# 4_mcu_radio_1.net
KiCad netlist of a schematic drawn in Altium Designer
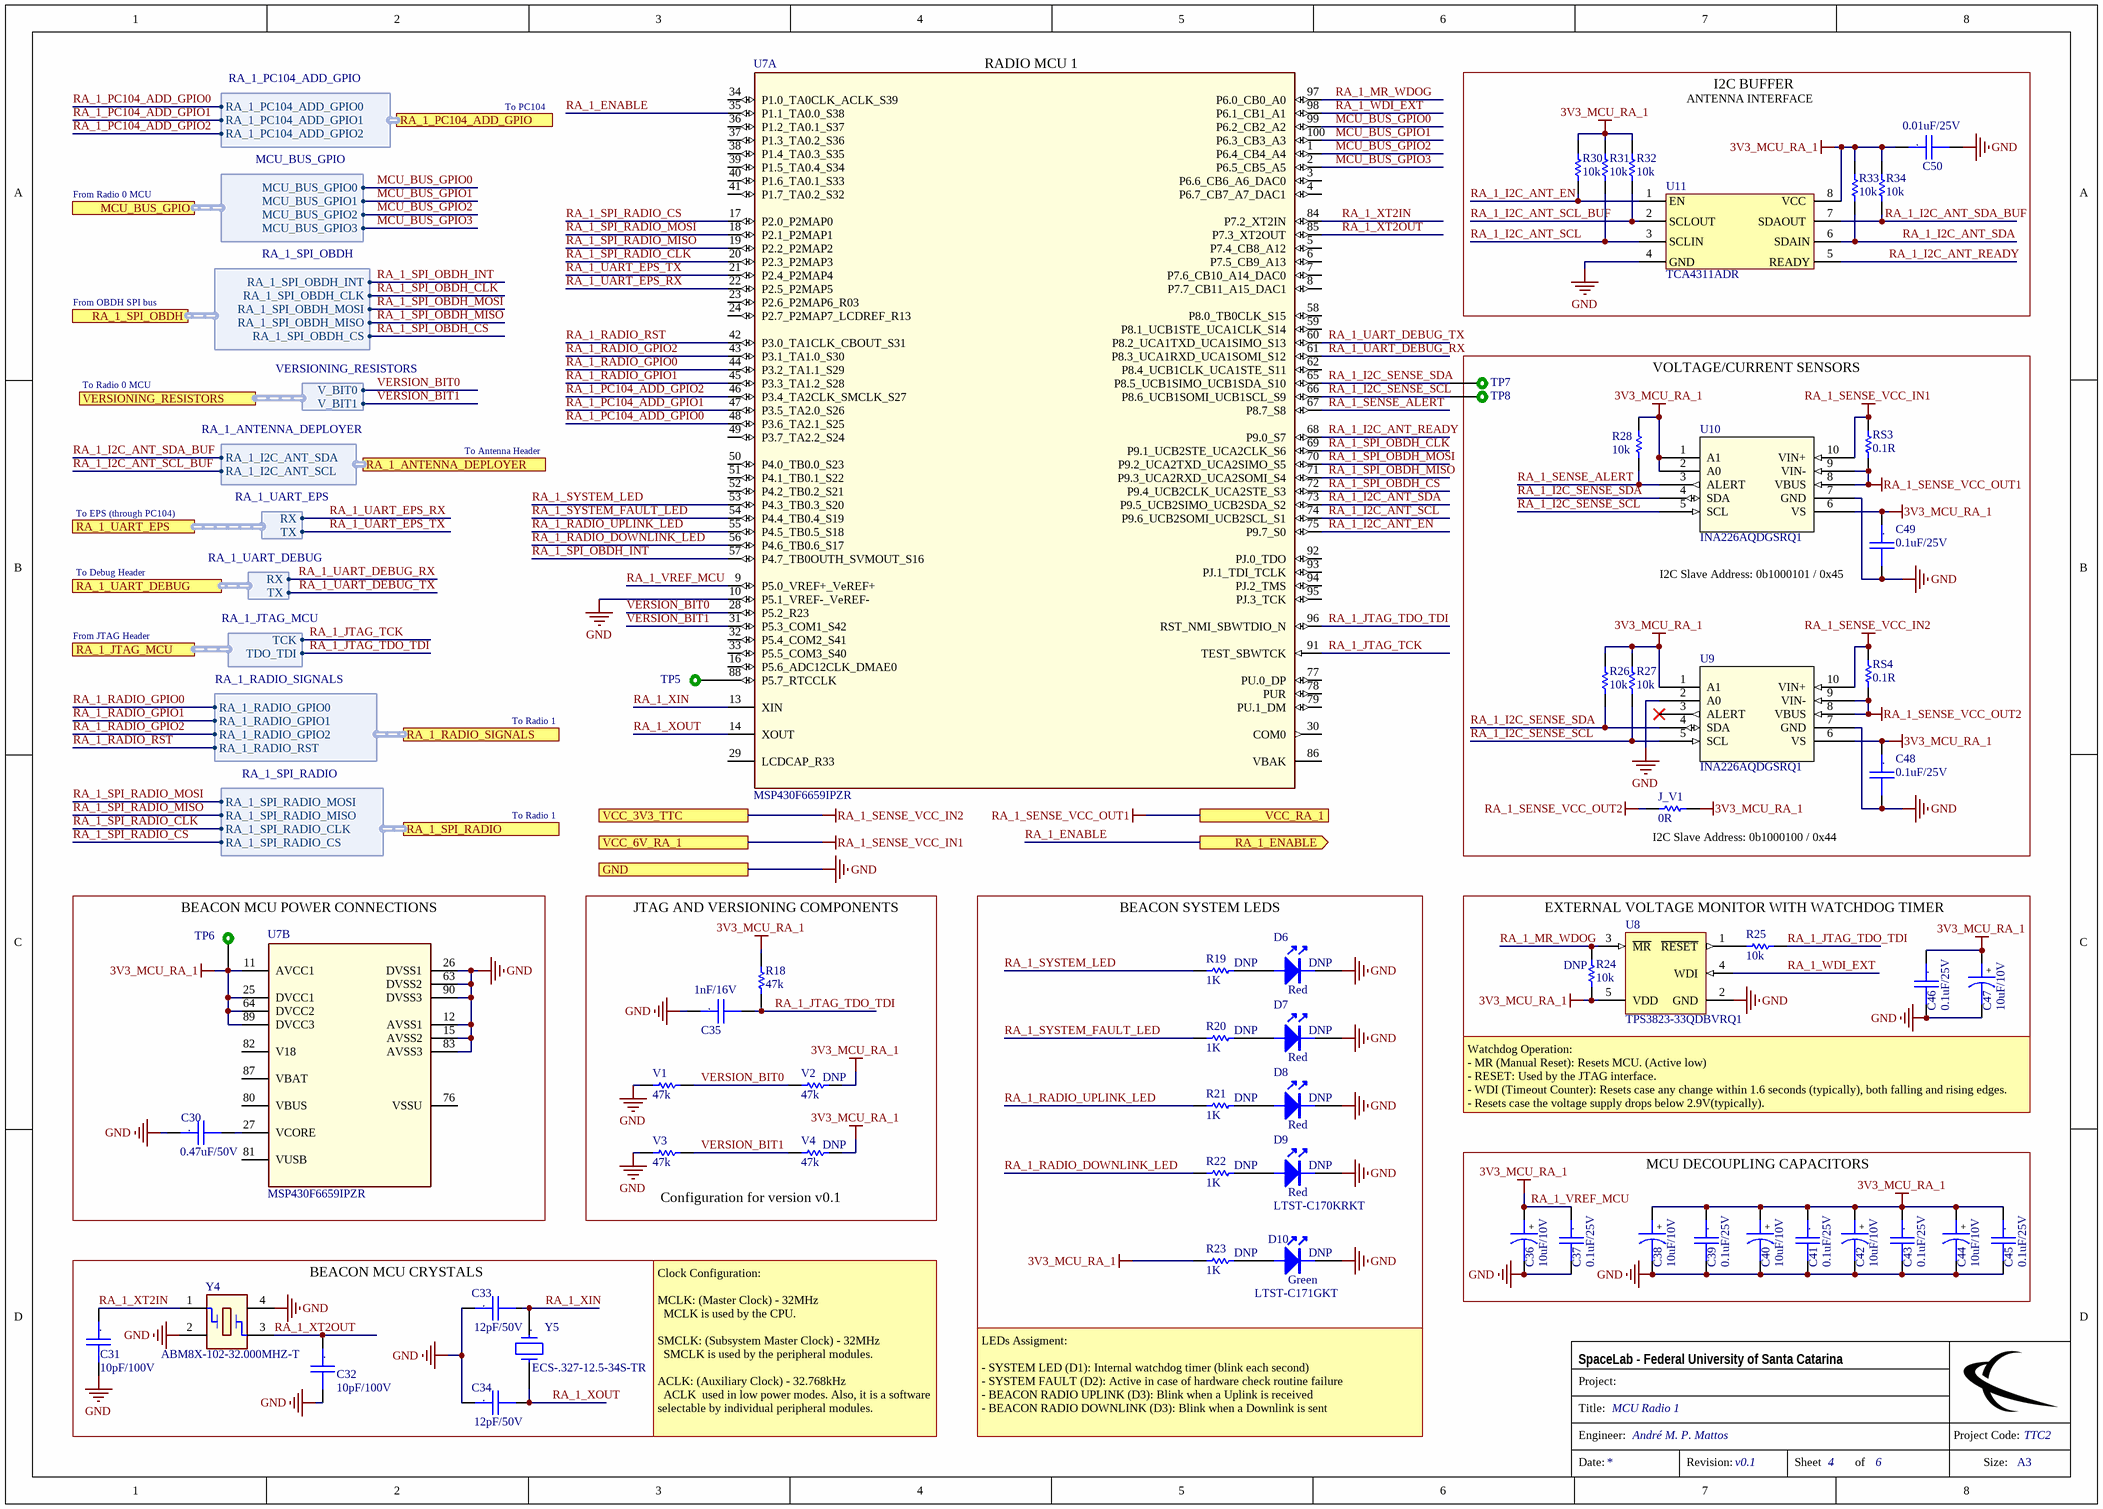
[diagram p0: 4_mcu_radio_1.schdoc]

(export (version "E")
  (design (tool "Eeschema 10.0.6"))
  (components
    (comp (ref "C30")
      (value "0.47uF/50V")
      (footprint "CC0805")
      (description "CAP CER 0.47UF 50V 10% X7R 0805")
      (fields (field (name "PARTNUMBER") "C0805C474K5RACTU"))
      (libsource (lib "schematics_library_legacy") (part "Cap_Cer_X7R_0.47uF_50V_0805"))
    )
    (comp (ref "C31")
      (value "10pF/100V")
      (footprint "CC0805")
      (description "CAP CER 10pF 100V 0805")
      (fields (field (name "PARTNUMBER") "08051A100FAT2A"))
      (libsource (lib "schematics_library_legacy") (part "Cap_Cer_X7R_10pF_100V_0805"))
    )
    (comp (ref "C32")
      (value "10pF/100V")
      (footprint "CC0805")
      (description "CAP CER 10pF 100V 0805")
      (fields (field (name "PARTNUMBER") "08051A100FAT2A"))
      (libsource (lib "schematics_library_legacy") (part "Cap_Cer_X7R_10pF_100V_0805"))
    )
    (comp (ref "C33")
      (value "12pF/50V")
      (footprint "CC0805")
      (description "CAP CER 12pF 50V 0805")
      (fields (field (name "PARTNUMBER") "CL21C120FBANNNC"))
      (libsource (lib "schematics_library_legacy") (part "Cap_Cer_X7R_12pF_50V_0805"))
    )
    (comp (ref "C34")
      (value "12pF/50V")
      (footprint "CC0805")
      (description "CAP CER 12pF 50V 0805")
      (fields (field (name "PARTNUMBER") "CL21C120FBANNNC"))
      (libsource (lib "schematics_library_legacy") (part "Cap_Cer_X7R_12pF_50V_0805"))
    )
    (comp (ref "C35")
      (value "1nF/16V")
      (footprint "CC0603")
      (description "CAP CER 1nF 16V 0603 5%")
      (fields (field (name "PARTNUMBER") "C0603X102J4RECAUTO"))
      (libsource (lib "schematics_library_legacy") (part "Cap_Cer_X7R_1nF_16V_0603"))
    )
    (comp (ref "C36")
      (value "10uF/10V")
      (footprint "CC0805_Tantalum")
      (description "CAP Tantalum 10uF 10V 20% 0805")
      (fields (field (name "PARTNUMBER") "TPSP106M010R2000"))
      (libsource (lib "schematics_library_legacy") (part "Cap_Tant_SMD_10uF_10V_0805"))
    )
    (comp (ref "C37")
      (value "0.1uF/25V")
      (footprint "CC0805")
      (description "CAP CER 0.1UF 25V 10% X7R 0805")
      (fields (field (name "PARTNUMBER") "CC0805KRX7R8BB104"))
      (libsource (lib "schematics_library_legacy") (part "Cap_Cer_X7R_0.1uF_25V_0805"))
    )
    (comp (ref "C38")
      (value "10uF/10V")
      (footprint "CC0805_Tantalum")
      (description "CAP Tantalum 10uF 10V 20% 0805")
      (fields (field (name "PARTNUMBER") "TPSP106M010R2000"))
      (libsource (lib "schematics_library_legacy") (part "Cap_Tant_SMD_10uF_10V_0805"))
    )
    (comp (ref "C39")
      (value "0.1uF/25V")
      (footprint "CC0805")
      (description "CAP CER 0.1UF 25V 10% X7R 0805")
      (fields (field (name "PARTNUMBER") "CC0805KRX7R8BB104"))
      (libsource (lib "schematics_library_legacy") (part "Cap_Cer_X7R_0.1uF_25V_0805"))
    )
    (comp (ref "C40")
      (value "10uF/10V")
      (footprint "CC0805_Tantalum")
      (description "CAP Tantalum 10uF 10V 20% 0805")
      (fields (field (name "PARTNUMBER") "TPSP106M010R2000"))
      (libsource (lib "schematics_library_legacy") (part "Cap_Tant_SMD_10uF_10V_0805"))
    )
    (comp (ref "C41")
      (value "0.1uF/25V")
      (footprint "CC0805")
      (description "CAP CER 0.1UF 25V 10% X7R 0805")
      (fields (field (name "PARTNUMBER") "CC0805KRX7R8BB104"))
      (libsource (lib "schematics_library_legacy") (part "Cap_Cer_X7R_0.1uF_25V_0805"))
    )
    (comp (ref "C42")
      (value "10uF/10V")
      (footprint "CC0805_Tantalum")
      (description "CAP Tantalum 10uF 10V 20% 0805")
      (fields (field (name "PARTNUMBER") "TPSP106M010R2000"))
      (libsource (lib "schematics_library_legacy") (part "Cap_Tant_SMD_10uF_10V_0805"))
    )
    (comp (ref "C43")
      (value "0.1uF/25V")
      (footprint "CC0805")
      (description "CAP CER 0.1UF 25V 10% X7R 0805")
      (fields (field (name "PARTNUMBER") "CC0805KRX7R8BB104"))
      (libsource (lib "schematics_library_legacy") (part "Cap_Cer_X7R_0.1uF_25V_0805"))
    )
    (comp (ref "C44")
      (value "10uF/10V")
      (footprint "CC0805_Tantalum")
      (description "CAP Tantalum 10uF 10V 20% 0805")
      (fields (field (name "PARTNUMBER") "TPSP106M010R2000"))
      (libsource (lib "schematics_library_legacy") (part "Cap_Tant_SMD_10uF_10V_0805"))
    )
    (comp (ref "C45")
      (value "0.1uF/25V")
      (footprint "CC0805")
      (description "CAP CER 0.1UF 25V 10% X7R 0805")
      (fields (field (name "PARTNUMBER") "CC0805KRX7R8BB104"))
      (libsource (lib "schematics_library_legacy") (part "Cap_Cer_X7R_0.1uF_25V_0805"))
    )
    (comp (ref "C46")
      (value "0.1uF/25V")
      (footprint "CC0805")
      (description "CAP CER 0.1UF 25V 10% X7R 0805")
      (fields (field (name "PARTNUMBER") "CC0805KRX7R8BB104"))
      (libsource (lib "schematics_library_legacy") (part "Cap_Cer_X7R_0.1uF_25V_0805"))
    )
    (comp (ref "C47")
      (value "10uF/10V")
      (footprint "CC0805_Tantalum")
      (description "CAP Tantalum 10uF 10V 20% 0805")
      (fields (field (name "PARTNUMBER") "TPSP106M010R2000"))
      (libsource (lib "schematics_library_legacy") (part "Cap_Tant_SMD_10uF_10V_0805"))
    )
    (comp (ref "C48")
      (value "0.1uF/25V")
      (footprint "CC0805")
      (description "CAP CER 0.1UF 25V 10% X7R 0805")
      (fields (field (name "PARTNUMBER") "CC0805KRX7R8BB104"))
      (libsource (lib "schematics_library_legacy") (part "Cap_Cer_X7R_0.1uF_25V_0805"))
    )
    (comp (ref "C49")
      (value "0.1uF/25V")
      (footprint "CC0805")
      (description "CAP CER 0.1UF 25V 10% X7R 0805")
      (fields (field (name "PARTNUMBER") "CC0805KRX7R8BB104"))
      (libsource (lib "schematics_library_legacy") (part "Cap_Cer_X7R_0.1uF_25V_0805"))
    )
    (comp (ref "C50")
      (value "0.01uF/25V")
      (footprint "CC0805")
      (description "CAP CER 0.01uF 25V 10% X7R 0805")
      (fields (field (name "PARTNUMBER") "CL21B103KAANNNC"))
      (libsource (lib "schematics_library_legacy") (part "Cap_Cer_X7R_0.01uF_25V_0805"))
    )
    (comp (ref "D6")
      (value "LTST-C170KRKT")
      (footprint "0805-RED-LED")
      (description "LED Red SMD - Red 631nm LED Indication, Discrete 2V 0805 (2012 Metric)")
      (libsource (lib "schematics_library_legacy") (part "LED/R_0805"))
    )
    (comp (ref "D7")
      (value "LTST-C170KRKT")
      (footprint "0805-RED-LED")
      (description "LED Red SMD - Red 631nm LED Indication, Discrete 2V 0805 (2012 Metric)")
      (libsource (lib "schematics_library_legacy") (part "LED/R_0805"))
    )
    (comp (ref "D8")
      (value "LTST-C170KRKT")
      (footprint "0805-RED-LED")
      (description "LED Red SMD - Red 631nm LED Indication, Discrete 2V 0805 (2012 Metric)")
      (libsource (lib "schematics_library_legacy") (part "LED/R_0805"))
    )
    (comp (ref "D9")
      (value "LTST-C170KRKT")
      (footprint "0805-RED-LED")
      (description "LED Red SMD - Red 631nm LED Indication, Discrete 2V 0805 (2012 Metric)")
      (libsource (lib "schematics_library_legacy") (part "LED/R_0805"))
    )
    (comp (ref "D10")
      (value "LTST-C171GKT")
      (footprint "0805-GREEN-LED")
      (description "LED Green SMD - Green 569nm LED Indication - Discrete 2.1V 0805 (2012 Metric)")
      (libsource (lib "schematics_library_legacy") (part "LED/G_0805"))
    )
    (comp (ref "J_V1")
      (value "0R")
      (footprint "0805")
      (description "RES 0R OHM 1/8W JUMPER 0805")
      (fields (field (name "PARTNUMBER") "CRCW08050000Z0EA"))
      (libsource (lib "schematics_library_legacy") (part "R0R_JUMPER_1/8W_0805"))
    )
    (comp (ref "R18")
      (value "47k")
      (footprint "0805")
      (description "RES 47k OHM 1/8W 1% 0805")
      (fields (field (name "PARTNUMBER") "RC0805FR-0747KL"))
      (libsource (lib "schematics_library_legacy") (part "R47k_1%_1/8W_0805"))
    )
    (comp (ref "R19")
      (value "1K")
      (footprint "0805")
      (description "RES 1.0K OHM 1/8W 1% 0805")
      (fields (field (name "PARTNUMBER") "RC0805FR-071KL"))
      (libsource (lib "schematics_library_legacy") (part "R1.0k_1%_1/8W_0805"))
    )
    (comp (ref "R20")
      (value "1K")
      (footprint "0805")
      (description "RES 1.0K OHM 1/8W 1% 0805")
      (fields (field (name "PARTNUMBER") "RC0805FR-071KL"))
      (libsource (lib "schematics_library_legacy") (part "R1.0k_1%_1/8W_0805"))
    )
    (comp (ref "R21")
      (value "1K")
      (footprint "0805")
      (description "RES 1.0K OHM 1/8W 1% 0805")
      (fields (field (name "PARTNUMBER") "RC0805FR-071KL"))
      (libsource (lib "schematics_library_legacy") (part "R1.0k_1%_1/8W_0805"))
    )
    (comp (ref "R22")
      (value "1K")
      (footprint "0805")
      (description "RES 1.0K OHM 1/8W 1% 0805")
      (fields (field (name "PARTNUMBER") "RC0805FR-071KL"))
      (libsource (lib "schematics_library_legacy") (part "R1.0k_1%_1/8W_0805"))
    )
    (comp (ref "R23")
      (value "1K")
      (footprint "0805")
      (description "RES 1.0K OHM 1/8W 1% 0805")
      (fields (field (name "PARTNUMBER") "RC0805FR-071KL"))
      (libsource (lib "schematics_library_legacy") (part "R1.0k_1%_1/8W_0805"))
    )
    (comp (ref "R24")
      (value "10k")
      (footprint "0805")
      (description "RES 10K OHM 1/8W 1%  0805")
      (fields (field (name "PARTNUMBER") "CRCW080510K0FKEA"))
      (libsource (lib "schematics_library_legacy") (part "R10k_1%_1/8W_0805"))
    )
    (comp (ref "R25")
      (value "10k")
      (footprint "0805")
      (description "RES 10K OHM 1/8W 1%  0805")
      (fields (field (name "PARTNUMBER") "CRCW080510K0FKEA"))
      (libsource (lib "schematics_library_legacy") (part "R10k_1%_1/8W_0805"))
    )
    (comp (ref "R26")
      (value "10k")
      (footprint "0805")
      (description "RES 10K OHM 1/8W 1%  0805")
      (fields (field (name "PARTNUMBER") "CRCW080510K0FKEA"))
      (libsource (lib "schematics_library_legacy") (part "R10k_1%_1/8W_0805"))
    )
    (comp (ref "R27")
      (value "10k")
      (footprint "0805")
      (description "RES 10K OHM 1/8W 1%  0805")
      (fields (field (name "PARTNUMBER") "CRCW080510K0FKEA"))
      (libsource (lib "schematics_library_legacy") (part "R10k_1%_1/8W_0805"))
    )
    (comp (ref "R28")
      (value "10k")
      (footprint "0805")
      (description "RES 10K OHM 1/8W 1%  0805")
      (fields (field (name "PARTNUMBER") "CRCW080510K0FKEA"))
      (libsource (lib "schematics_library_legacy") (part "R10k_1%_1/8W_0805"))
    )
    (comp (ref "R30")
      (value "10k")
      (footprint "0805")
      (description "RES 10K OHM 1/8W 1%  0805")
      (fields (field (name "PARTNUMBER") "CRCW080510K0FKEA"))
      (libsource (lib "schematics_library_legacy") (part "R10k_1%_1/8W_0805"))
    )
    (comp (ref "R31")
      (value "10k")
      (footprint "0805")
      (description "RES 10K OHM 1/8W 1%  0805")
      (fields (field (name "PARTNUMBER") "CRCW080510K0FKEA"))
      (libsource (lib "schematics_library_legacy") (part "R10k_1%_1/8W_0805"))
    )
    (comp (ref "R32")
      (value "10k")
      (footprint "0805")
      (description "RES 10K OHM 1/8W 1%  0805")
      (fields (field (name "PARTNUMBER") "CRCW080510K0FKEA"))
      (libsource (lib "schematics_library_legacy") (part "R10k_1%_1/8W_0805"))
    )
    (comp (ref "R33")
      (value "10k")
      (footprint "0805")
      (description "RES 10K OHM 1/8W 1%  0805")
      (fields (field (name "PARTNUMBER") "CRCW080510K0FKEA"))
      (libsource (lib "schematics_library_legacy") (part "R10k_1%_1/8W_0805"))
    )
    (comp (ref "R34")
      (value "10k")
      (footprint "0805")
      (description "RES 10K OHM 1/8W 1%  0805")
      (fields (field (name "PARTNUMBER") "CRCW080510K0FKEA"))
      (libsource (lib "schematics_library_legacy") (part "R10k_1%_1/8W_0805"))
    )
    (comp (ref "RS3")
      (value "0.1R")
      (footprint "0805")
      (description "RES 0.1R OHM 1/3W 1% 0805")
      (fields (field (name "PARTNUMBER") "SR732ATTER100F"))
      (libsource (lib "schematics_library_legacy") (part "R0.1R_1%_1/3W_0805"))
    )
    (comp (ref "RS4")
      (value "0.1R")
      (footprint "0805")
      (description "RES 0.1R OHM 1/3W 1% 0805")
      (fields (field (name "PARTNUMBER") "SR732ATTER100F"))
      (libsource (lib "schematics_library_legacy") (part "R0.1R_1%_1/3W_0805"))
    )
    (comp (ref "TP5")
      (value "TEST_POINT")
      (footprint "TEST_POINT")
      (description "Test point")
      (libsource (lib "schematics_library_legacy") (part "TEST_POINT"))
    )
    (comp (ref "TP6")
      (value "TEST_POINT")
      (footprint "TEST_POINT")
      (description "Test point")
      (libsource (lib "schematics_library_legacy") (part "TEST_POINT"))
    )
    (comp (ref "TP7")
      (value "TEST_POINT")
      (footprint "TEST_POINT")
      (description "Test point")
      (libsource (lib "schematics_library_legacy") (part "TEST_POINT"))
    )
    (comp (ref "TP8")
      (value "TEST_POINT")
      (footprint "TEST_POINT")
      (description "Test point")
      (libsource (lib "schematics_library_legacy") (part "TEST_POINT"))
    )
    (comp (ref "U7")
      (value "MSP430F6659IPZR")
      (footprint "LQFP-100")
      (description "CPUXV2 series Microcontroller IC 16-Bit 20MHz 512KB (512K x 8) FLASH 100-LQFP (14x14)")
      (fields
        (field (name "ALTERNATE PARTNUMBER") "MSP430F6659IPZ")
        (field (name "MANUFACTURER") "Texas Instruments")
      )
      (libsource (lib "schematics_library_legacy") (part "MSP430F6659IPZR"))
    )
    (comp (ref "U8")
      (value "TPS3823-33QDBVRQ1")
      (footprint "DBV0005A_N")
      (fields (field (name "MANUFACTURER") "Texas Instruments"))
      (libsource (lib "schematics_library_legacy") (part "CMP-0338-00011-2"))
    )
    (comp (ref "U9")
      (value "INA226AQDGSRQ1")
      (footprint "DGS10")
      (description "High-Side Measurement, Bi-Directional Current/Power Monitor w/I2C Interface")
      (fields
        (field (name "MANUFACTURER") "Texas Instruments")
        (field (name "GENERIC_PART_NUMBER") "INA226")
        (field (name "COPYRIGHT") "Copyright (C) 2018 Accelerated Designs. All rights reserved")
      )
      (libsource (lib "schematics_library_legacy") (part "INA226AQDGSRQ1"))
    )
    (comp (ref "U10")
      (value "INA226AQDGSRQ1")
      (footprint "DGS10")
      (description "High-Side Measurement, Bi-Directional Current/Power Monitor w/I2C Interface")
      (fields
        (field (name "MANUFACTURER") "Texas Instruments")
        (field (name "GENERIC_PART_NUMBER") "INA226")
        (field (name "COPYRIGHT") "Copyright (C) 2018 Accelerated Designs. All rights reserved")
      )
      (libsource (lib "schematics_library_legacy") (part "INA226AQDGSRQ1"))
    )
    (comp (ref "U11")
      (value "TCA4311ADR")
      (footprint "SOIC8")
      (description "IC SIGNAL BUFFER I2C 8SOIC HOTSWAP")
      (libsource (lib "schematics_library_legacy") (part "TCA4311ADR"))
    )
    (comp (ref "V1")
      (value "47k")
      (footprint "0805")
      (description "RES 47k OHM 1/8W 1% 0805")
      (fields (field (name "PARTNUMBER") "RC0805FR-0747KL"))
      (libsource (lib "schematics_library_legacy") (part "R47k_1%_1/8W_0805"))
    )
    (comp (ref "V2")
      (value "47k")
      (footprint "0805")
      (description "RES 47k OHM 1/8W 1% 0805")
      (fields (field (name "PARTNUMBER") "RC0805FR-0747KL"))
      (libsource (lib "schematics_library_legacy") (part "R47k_1%_1/8W_0805"))
    )
    (comp (ref "V3")
      (value "47k")
      (footprint "0805")
      (description "RES 47k OHM 1/8W 1% 0805")
      (fields (field (name "PARTNUMBER") "RC0805FR-0747KL"))
      (libsource (lib "schematics_library_legacy") (part "R47k_1%_1/8W_0805"))
    )
    (comp (ref "V4")
      (value "47k")
      (footprint "0805")
      (description "RES 47k OHM 1/8W 1% 0805")
      (fields (field (name "PARTNUMBER") "RC0805FR-0747KL"))
      (libsource (lib "schematics_library_legacy") (part "R47k_1%_1/8W_0805"))
    )
    (comp (ref "Y4")
      (value "ABM8X-102-32.000MHZ-T")
      (footprint "XTAL_ABM8X")
      (description "32MHz ±10ppm Crystal 10pF 60 Ohm -40°C ~ 125°C")
      (libsource (lib "schematics_library_legacy") (part "XTAL_32MHz_SMD_4-SMD"))
    )
    (comp (ref "Y5")
      (value "ECS-.327-12.5-34S-TR")
      (footprint "ABS06 0805")
      (description "32.768kHz ±20ppm Crystal 12.5pF 70 kOhm -40°C ~ 125°C")
      (libsource (lib "schematics_library_legacy") (part "Xtal_32.768kHz_12pF_2_SMD"))
    )
  )
  (nets
    (net (code "12") (name "/MCU_BUS_GPIO0") (class "Default")
      (node (ref "U7") (pin "99") (pinfunction "P6.2_CB2_A2_99") (pintype "bidirectional"))
    )
    (net (code "13") (name "/MCU_BUS_GPIO1") (class "Default")
      (node (ref "U7") (pin "100") (pinfunction "P6.3_CB3_A3_100") (pintype "bidirectional"))
    )
    (net (code "14") (name "/MCU_BUS_GPIO2") (class "Default")
      (node (ref "U7") (pin "1") (pinfunction "P6.4_CB4_A4_1") (pintype "bidirectional"))
    )
    (net (code "15") (name "/MCU_BUS_GPIO3") (class "Default")
      (node (ref "U7") (pin "2") (pinfunction "P6.5_CB5_A5_2") (pintype "bidirectional"))
    )
    (net (code "16") (name "/RA_1_ENABLE") (class "Default")
      (node (ref "U7") (pin "35") (pinfunction "P1.1_TA0.0_S38_35") (pintype "bidirectional"))
    )
    (net (code "17") (name "/RA_1_I2C_ANT_EN") (class "Default")
      (node (ref "R30") (pin "1") (pinfunction "1_1") (pintype "passive"))
      (node (ref "U11") (pin "1") (pinfunction "EN_1") (pintype "passive"))
      (node (ref "U7") (pin "75") (pinfunction "P9.7_S0_75") (pintype "bidirectional"))
    )
    (net (code "18") (name "/RA_1_I2C_ANT_READY") (class "Default")
      (node (ref "U11") (pin "5") (pinfunction "READY_5") (pintype "passive"))
      (node (ref "U7") (pin "68") (pinfunction "P9.0_S7_68") (pintype "bidirectional"))
    )
    (net (code "19") (name "/RA_1_I2C_ANT_SCL") (class "Default")
      (node (ref "R31") (pin "1") (pinfunction "1_1") (pintype "passive"))
      (node (ref "U11") (pin "3") (pinfunction "SCLIN_3") (pintype "passive"))
      (node (ref "U7") (pin "74") (pinfunction "P9.6_UCB2SOMI_UCB2SCL_S1_74") (pintype "bidirectional"))
    )
    (net (code "20") (name "/RA_1_I2C_ANT_SCL_BUF") (class "Default")
      (node (ref "R32") (pin "1") (pinfunction "1_1") (pintype "passive"))
      (node (ref "U11") (pin "2") (pinfunction "SCLOUT_2") (pintype "passive"))
    )
    (net (code "21") (name "/RA_1_I2C_ANT_SDA") (class "Default")
      (node (ref "R33") (pin "1") (pinfunction "1_1") (pintype "passive"))
      (node (ref "U11") (pin "6") (pinfunction "SDAIN_6") (pintype "passive"))
      (node (ref "U7") (pin "73") (pinfunction "P9.5_UCB2SIMO_UCB2SDA_S2_73") (pintype "bidirectional"))
    )
    (net (code "22") (name "/RA_1_I2C_ANT_SDA_BUF") (class "Default")
      (node (ref "R34") (pin "1") (pinfunction "1_1") (pintype "passive"))
      (node (ref "U11") (pin "7") (pinfunction "SDAOUT_7") (pintype "passive"))
    )
    (net (code "23") (name "/RA_1_I2C_SENSE_SCL") (class "Default")
      (node (ref "R27") (pin "1") (pinfunction "1_1") (pintype "passive"))
      (node (ref "TP8") (pin "1") (pinfunction "1_1") (pintype "passive"))
      (node (ref "U10") (pin "5") (pinfunction "SCL_5") (pintype "input"))
      (node (ref "U7") (pin "66") (pinfunction "P8.6_UCB1SOMI_UCB1SCL_S9_66") (pintype "bidirectional"))
      (node (ref "U9") (pin "5") (pinfunction "SCL_5") (pintype "input"))
    )
    (net (code "24") (name "/RA_1_I2C_SENSE_SDA") (class "Default")
      (node (ref "R26") (pin "1") (pinfunction "1_1") (pintype "passive"))
      (node (ref "TP7") (pin "1") (pinfunction "1_1") (pintype "passive"))
      (node (ref "U10") (pin "4") (pinfunction "SDA_4") (pintype "bidirectional"))
      (node (ref "U7") (pin "65") (pinfunction "P8.5_UCB1SIMO_UCB1SDA_S10_65") (pintype "bidirectional"))
      (node (ref "U9") (pin "4") (pinfunction "SDA_4") (pintype "bidirectional"))
    )
    (net (code "25") (name "/RA_1_JTAG_TCK") (class "Default")
      (node (ref "U7") (pin "91") (pinfunction "TEST_SBWTCK_91") (pintype "input"))
    )
    (net (code "26") (name "/RA_1_JTAG_TDO_TDI") (class "Default")
      (node (ref "C35") (pin "2") (pinfunction "2_2") (pintype "passive"))
      (node (ref "R18") (pin "1") (pinfunction "1_1") (pintype "passive"))
      (node (ref "R25") (pin "1") (pinfunction "1_1") (pintype "passive"))
      (node (ref "U7") (pin "96") (pinfunction "RST_NMI_SBWTDIO_N_96") (pintype "bidirectional"))
    )
    (net (code "27") (name "/RA_1_MR_WDOG") (class "Default")
      (node (ref "R24") (pin "2") (pinfunction "2_2") (pintype "passive"))
      (node (ref "U7") (pin "97") (pinfunction "P6.0_CB0_A0_97") (pintype "bidirectional"))
      (node (ref "U8") (pin "3") (pinfunction "~{MR}_3") (pintype "input"))
    )
    (net (code "28") (name "/RA_1_PC104_ADD_GPIO0") (class "Default")
      (node (ref "U7") (pin "48") (pinfunction "P3.6_TA2.1_S25_48") (pintype "bidirectional"))
    )
    (net (code "29") (name "/RA_1_PC104_ADD_GPIO1") (class "Default")
      (node (ref "U7") (pin "47") (pinfunction "P3.5_TA2.0_S26_47") (pintype "bidirectional"))
    )
    (net (code "30") (name "/RA_1_PC104_ADD_GPIO2") (class "Default")
      (node (ref "U7") (pin "46") (pinfunction "P3.4_TA2CLK_SMCLK_S27_46") (pintype "bidirectional"))
    )
    (net (code "31") (name "/RA_1_RADIO_DOWNLINK_LED") (class "Default")
      (node (ref "R22") (pin "2") (pinfunction "2_2") (pintype "passive"))
      (node (ref "U7") (pin "56") (pinfunction "P4.6_TB0.6_S17_56") (pintype "bidirectional"))
    )
    (net (code "32") (name "/RA_1_RADIO_GPIO0") (class "Default")
      (node (ref "U7") (pin "44") (pinfunction "P3.2_TA1.1_S29_44") (pintype "bidirectional"))
    )
    (net (code "33") (name "/RA_1_RADIO_GPIO1") (class "Default")
      (node (ref "U7") (pin "45") (pinfunction "P3.3_TA1.2_S28_45") (pintype "bidirectional"))
    )
    (net (code "34") (name "/RA_1_RADIO_GPIO2") (class "Default")
      (node (ref "U7") (pin "43") (pinfunction "P3.1_TA1.0_S30_43") (pintype "bidirectional"))
    )
    (net (code "35") (name "/RA_1_RADIO_RST") (class "Default")
      (node (ref "U7") (pin "42") (pinfunction "P3.0_TA1CLK_CBOUT_S31_42") (pintype "bidirectional"))
    )
    (net (code "36") (name "/RA_1_RADIO_UPLINK_LED") (class "Default")
      (node (ref "R21") (pin "2") (pinfunction "2_2") (pintype "passive"))
      (node (ref "U7") (pin "55") (pinfunction "P4.5_TB0.5_S18_55") (pintype "bidirectional"))
    )
    (net (code "37") (name "/RA_1_SENSE_ALERT") (class "Default")
      (node (ref "R28") (pin "1") (pinfunction "1_1") (pintype "passive"))
      (node (ref "U10") (pin "3") (pinfunction "ALERT_3") (pintype "output"))
      (node (ref "U7") (pin "67") (pinfunction "P8.7_S8_67") (pintype "bidirectional"))
    )
    (net (code "38") (name "/RA_1_SPI_OBDH_CLK") (class "Default")
      (node (ref "U7") (pin "69") (pinfunction "P9.1_UCB2STE_UCA2CLK_S6_69") (pintype "bidirectional"))
    )
    (net (code "39") (name "/RA_1_SPI_OBDH_CS") (class "Default")
      (node (ref "U7") (pin "72") (pinfunction "P9.4_UCB2CLK_UCA2STE_S3_72") (pintype "bidirectional"))
    )
    (net (code "40") (name "/RA_1_SPI_OBDH_INT") (class "Default")
      (node (ref "U7") (pin "57") (pinfunction "P4.7_TB0OUTH_SVMOUT_S16_57") (pintype "bidirectional"))
    )
    (net (code "41") (name "/RA_1_SPI_OBDH_MISO") (class "Default")
      (node (ref "U7") (pin "71") (pinfunction "P9.3_UCA2RXD_UCA2SOMI_S4_71") (pintype "bidirectional"))
    )
    (net (code "42") (name "/RA_1_SPI_OBDH_MOSI") (class "Default")
      (node (ref "U7") (pin "70") (pinfunction "P9.2_UCA2TXD_UCA2SIMO_S5_70") (pintype "bidirectional"))
    )
    (net (code "43") (name "/RA_1_SPI_RADIO_CLK") (class "Default")
      (node (ref "U7") (pin "20") (pinfunction "P2.3_P2MAP3_20") (pintype "bidirectional"))
    )
    (net (code "44") (name "/RA_1_SPI_RADIO_CS") (class "Default")
      (node (ref "U7") (pin "17") (pinfunction "P2.0_P2MAP0_17") (pintype "bidirectional"))
    )
    (net (code "45") (name "/RA_1_SPI_RADIO_MISO") (class "Default")
      (node (ref "U7") (pin "19") (pinfunction "P2.2_P2MAP2_19") (pintype "bidirectional"))
    )
    (net (code "46") (name "/RA_1_SPI_RADIO_MOSI") (class "Default")
      (node (ref "U7") (pin "18") (pinfunction "P2.1_P2MAP1_18") (pintype "bidirectional"))
    )
    (net (code "47") (name "/RA_1_SYSTEM_FAULT_LED") (class "Default")
      (node (ref "R20") (pin "2") (pinfunction "2_2") (pintype "passive"))
      (node (ref "U7") (pin "54") (pinfunction "P4.4_TB0.4_S19_54") (pintype "bidirectional"))
    )
    (net (code "48") (name "/RA_1_SYSTEM_LED") (class "Default")
      (node (ref "R19") (pin "2") (pinfunction "2_2") (pintype "passive"))
      (node (ref "U7") (pin "53") (pinfunction "P4.3_TB0.3_S20_53") (pintype "bidirectional"))
    )
    (net (code "49") (name "/RA_1_UART_DEBUG_RX") (class "Default")
      (node (ref "U7") (pin "61") (pinfunction "P8.3_UCA1RXD_UCA1SOMI_S12_61") (pintype "bidirectional"))
    )
    (net (code "50") (name "/RA_1_UART_DEBUG_TX") (class "Default")
      (node (ref "U7") (pin "60") (pinfunction "P8.2_UCA1TXD_UCA1SIMO_S13_60") (pintype "bidirectional"))
    )
    (net (code "51") (name "/RA_1_UART_EPS_RX") (class "Default")
      (node (ref "U7") (pin "22") (pinfunction "P2.5_P2MAP5_22") (pintype "bidirectional"))
    )
    (net (code "52") (name "/RA_1_UART_EPS_TX") (class "Default")
      (node (ref "U7") (pin "21") (pinfunction "P2.4_P2MAP4_21") (pintype "bidirectional"))
    )
    (net (code "53") (name "/RA_1_WDI_EXT") (class "Default")
      (node (ref "U7") (pin "98") (pinfunction "P6.1_CB1_A1_98") (pintype "bidirectional"))
      (node (ref "U8") (pin "4") (pinfunction "WDI_4") (pintype "input"))
    )
    (net (code "54") (name "/RA_1_XIN") (class "Default")
      (node (ref "C33") (pin "2") (pinfunction "2_2") (pintype "passive"))
      (node (ref "U7") (pin "13") (pinfunction "XIN_13") (pintype "passive"))
      (node (ref "Y5") (pin "1") (pinfunction "1_1") (pintype "passive"))
    )
    (net (code "55") (name "/RA_1_XOUT") (class "Default")
      (node (ref "C34") (pin "2") (pinfunction "2_2") (pintype "passive"))
      (node (ref "U7") (pin "14") (pinfunction "XOUT_14") (pintype "passive"))
      (node (ref "Y5") (pin "2") (pinfunction "2_2") (pintype "passive"))
    )
    (net (code "56") (name "/RA_1_XT2IN") (class "Default")
      (node (ref "C31") (pin "1") (pinfunction "1_1") (pintype "passive"))
      (node (ref "U7") (pin "84") (pinfunction "P7.2_XT2IN_84") (pintype "bidirectional"))
      (node (ref "Y4") (pin "1") (pinfunction "1_1") (pintype "passive"))
    )
    (net (code "57") (name "/RA_1_XT2OUT") (class "Default")
      (node (ref "C32") (pin "1") (pinfunction "1_1") (pintype "passive"))
      (node (ref "U7") (pin "85") (pinfunction "P7.3_XT2OUT_85") (pintype "bidirectional"))
      (node (ref "Y4") (pin "3") (pinfunction "3_3") (pintype "passive"))
    )
    (net (code "58") (name "/VERSION_BIT0") (class "Default")
      (node (ref "U7") (pin "28") (pinfunction "P5.2_R23_28") (pintype "bidirectional"))
      (node (ref "V1") (pin "1") (pinfunction "1_1") (pintype "passive"))
      (node (ref "V2") (pin "2") (pinfunction "2_2") (pintype "passive"))
    )
    (net (code "59") (name "/VERSION_BIT1") (class "Default")
      (node (ref "U7") (pin "31") (pinfunction "P5.3_COM1_S42_31") (pintype "bidirectional"))
      (node (ref "V3") (pin "1") (pinfunction "1_1") (pintype "passive"))
      (node (ref "V4") (pin "2") (pinfunction "2_2") (pintype "passive"))
    )
    (net (code "70") (name "3V3_MCU_RA_1") (class "Default")
      (node (ref "C36") (pin "1") (pinfunction "1_1") (pintype "passive"))
      (node (ref "C37") (pin "1") (pinfunction "1_1") (pintype "passive"))
      (node (ref "C38") (pin "1") (pinfunction "1_1") (pintype "passive"))
      (node (ref "C39") (pin "1") (pinfunction "1_1") (pintype "passive"))
      (node (ref "C40") (pin "1") (pinfunction "1_1") (pintype "passive"))
      (node (ref "C41") (pin "1") (pinfunction "1_1") (pintype "passive"))
      (node (ref "C42") (pin "1") (pinfunction "1_1") (pintype "passive"))
      (node (ref "C43") (pin "1") (pinfunction "1_1") (pintype "passive"))
      (node (ref "C44") (pin "1") (pinfunction "1_1") (pintype "passive"))
      (node (ref "C45") (pin "1") (pinfunction "1_1") (pintype "passive"))
      (node (ref "C46") (pin "1") (pinfunction "1_1") (pintype "passive"))
      (node (ref "C47") (pin "1") (pinfunction "1_1") (pintype "passive"))
      (node (ref "C48") (pin "1") (pinfunction "1_1") (pintype "passive"))
      (node (ref "C49") (pin "1") (pinfunction "1_1") (pintype "passive"))
      (node (ref "C50") (pin "1") (pinfunction "1_1") (pintype "passive"))
      (node (ref "J_V1") (pin "1") (pinfunction "1_1") (pintype "passive"))
      (node (ref "R18") (pin "2") (pinfunction "2_2") (pintype "passive"))
      (node (ref "R23") (pin "2") (pinfunction "2_2") (pintype "passive"))
      (node (ref "R24") (pin "1") (pinfunction "1_1") (pintype "passive"))
      (node (ref "R26") (pin "2") (pinfunction "2_2") (pintype "passive"))
      (node (ref "R27") (pin "2") (pinfunction "2_2") (pintype "passive"))
      (node (ref "R28") (pin "2") (pinfunction "2_2") (pintype "passive"))
      (node (ref "R30") (pin "2") (pinfunction "2_2") (pintype "passive"))
      (node (ref "R31") (pin "2") (pinfunction "2_2") (pintype "passive"))
      (node (ref "R32") (pin "2") (pinfunction "2_2") (pintype "passive"))
      (node (ref "R33") (pin "2") (pinfunction "2_2") (pintype "passive"))
      (node (ref "R34") (pin "2") (pinfunction "2_2") (pintype "passive"))
      (node (ref "TP6") (pin "1") (pinfunction "1_1") (pintype "passive"))
      (node (ref "U10") (pin "1") (pinfunction "A1_1") (pintype "passive"))
      (node (ref "U10") (pin "2") (pinfunction "A0_2") (pintype "passive"))
      (node (ref "U10") (pin "6") (pinfunction "VS_6") (pintype "power_in"))
      (node (ref "U11") (pin "8") (pinfunction "VCC_8") (pintype "power_in"))
      (node (ref "U7") (pin "11") (pinfunction "AVCC1_11") (pintype "power_in"))
      (node (ref "U7") (pin "25") (pinfunction "DVCC1_25") (pintype "power_in"))
      (node (ref "U7") (pin "64") (pinfunction "DVCC2_64") (pintype "power_in"))
      (node (ref "U7") (pin "89") (pinfunction "DVCC3_89") (pintype "power_in"))
      (node (ref "U7") (pin "9") (pinfunction "P5.0_VREF+_VeREF+_9") (pintype "bidirectional"))
      (node (ref "U8") (pin "5") (pinfunction "VDD_5") (pintype "power_in"))
      (node (ref "U9") (pin "1") (pinfunction "A1_1") (pintype "passive"))
      (node (ref "U9") (pin "6") (pinfunction "VS_6") (pintype "power_in"))
      (node (ref "V2") (pin "1") (pinfunction "1_1") (pintype "passive"))
      (node (ref "V4") (pin "1") (pinfunction "1_1") (pintype "passive"))
    )
    (net (code "71") (name "GND") (class "Default")
      (node (ref "C30") (pin "1") (pinfunction "1_1") (pintype "passive"))
      (node (ref "C31") (pin "2") (pinfunction "2_2") (pintype "passive"))
      (node (ref "C32") (pin "2") (pinfunction "2_2") (pintype "passive"))
      (node (ref "C33") (pin "1") (pinfunction "1_1") (pintype "passive"))
      (node (ref "C34") (pin "1") (pinfunction "1_1") (pintype "passive"))
      (node (ref "C35") (pin "1") (pinfunction "1_1") (pintype "passive"))
      (node (ref "C36") (pin "2") (pinfunction "2_2") (pintype "passive"))
      (node (ref "C37") (pin "2") (pinfunction "2_2") (pintype "passive"))
      (node (ref "C38") (pin "2") (pinfunction "2_2") (pintype "passive"))
      (node (ref "C39") (pin "2") (pinfunction "2_2") (pintype "passive"))
      (node (ref "C40") (pin "2") (pinfunction "2_2") (pintype "passive"))
      (node (ref "C41") (pin "2") (pinfunction "2_2") (pintype "passive"))
      (node (ref "C42") (pin "2") (pinfunction "2_2") (pintype "passive"))
      (node (ref "C43") (pin "2") (pinfunction "2_2") (pintype "passive"))
      (node (ref "C44") (pin "2") (pinfunction "2_2") (pintype "passive"))
      (node (ref "C45") (pin "2") (pinfunction "2_2") (pintype "passive"))
      (node (ref "C46") (pin "2") (pinfunction "2_2") (pintype "passive"))
      (node (ref "C47") (pin "2") (pinfunction "2_2") (pintype "passive"))
      (node (ref "C48") (pin "2") (pinfunction "2_2") (pintype "passive"))
      (node (ref "C49") (pin "2") (pinfunction "2_2") (pintype "passive"))
      (node (ref "C50") (pin "2") (pinfunction "2_2") (pintype "passive"))
      (node (ref "D10") (pin "2") (pinfunction "K_2") (pintype "passive"))
      (node (ref "D6") (pin "2") (pinfunction "K_2") (pintype "passive"))
      (node (ref "D7") (pin "2") (pinfunction "K_2") (pintype "passive"))
      (node (ref "D8") (pin "2") (pinfunction "K_2") (pintype "passive"))
      (node (ref "D9") (pin "2") (pinfunction "K_2") (pintype "passive"))
      (node (ref "U10") (pin "7") (pinfunction "GND_7") (pintype "power_in"))
      (node (ref "U11") (pin "4") (pinfunction "GND_4") (pintype "passive"))
      (node (ref "U7") (pin "10") (pinfunction "P5.1_VREF-_VeREF-_10") (pintype "bidirectional"))
      (node (ref "U7") (pin "12") (pinfunction "AVSS1_12") (pintype "power_in"))
      (node (ref "U7") (pin "15") (pinfunction "AVSS2_15") (pintype "power_in"))
      (node (ref "U7") (pin "26") (pinfunction "DVSS1_26") (pintype "passive"))
      (node (ref "U7") (pin "63") (pinfunction "DVSS2_63") (pintype "power_in"))
      (node (ref "U7") (pin "83") (pinfunction "AVSS3_83") (pintype "power_in"))
      (node (ref "U7") (pin "90") (pinfunction "DVSS3_90") (pintype "passive"))
      (node (ref "U8") (pin "2") (pinfunction "GND_2") (pintype "power_in"))
      (node (ref "U9") (pin "2") (pinfunction "A0_2") (pintype "passive"))
      (node (ref "U9") (pin "7") (pinfunction "GND_7") (pintype "power_in"))
      (node (ref "V1") (pin "2") (pinfunction "2_2") (pintype "passive"))
      (node (ref "V3") (pin "2") (pinfunction "2_2") (pintype "passive"))
      (node (ref "Y4") (pin "2") (pinfunction "2_2") (pintype "passive"))
      (node (ref "Y4") (pin "4") (pinfunction "4_4") (pintype "passive"))
    )
    (net (code "72") (name "Net-(D6-A)") (class "Default")
      (node (ref "D6") (pin "1") (pinfunction "A_1") (pintype "passive"))
      (node (ref "R19") (pin "1") (pinfunction "1_1") (pintype "passive"))
    )
    (net (code "73") (name "Net-(D7-A)") (class "Default")
      (node (ref "D7") (pin "1") (pinfunction "A_1") (pintype "passive"))
      (node (ref "R20") (pin "1") (pinfunction "1_1") (pintype "passive"))
    )
    (net (code "74") (name "Net-(D8-A)") (class "Default")
      (node (ref "D8") (pin "1") (pinfunction "A_1") (pintype "passive"))
      (node (ref "R21") (pin "1") (pinfunction "1_1") (pintype "passive"))
    )
    (net (code "75") (name "Net-(D9-A)") (class "Default")
      (node (ref "D9") (pin "1") (pinfunction "A_1") (pintype "passive"))
      (node (ref "R22") (pin "1") (pinfunction "1_1") (pintype "passive"))
    )
    (net (code "76") (name "Net-(D10-A)") (class "Default")
      (node (ref "D10") (pin "1") (pinfunction "A_1") (pintype "passive"))
      (node (ref "R23") (pin "1") (pinfunction "1_1") (pintype "passive"))
    )
    (net (code "77") (name "Net-(U7A-P5.7_RTCCLK)") (class "Default")
      (node (ref "TP5") (pin "1") (pinfunction "1_1") (pintype "passive"))
      (node (ref "U7") (pin "88") (pinfunction "P5.7_RTCCLK_88") (pintype "bidirectional"))
    )
    (net (code "78") (name "Net-(U7B-VCORE)") (class "Default")
      (node (ref "C30") (pin "2") (pinfunction "2_2") (pintype "passive"))
      (node (ref "U7") (pin "27") (pinfunction "VCORE_27") (pintype "power_in"))
    )
    (net (code "79") (name "Net-(U8-~{RESET})") (class "Default")
      (node (ref "R25") (pin "2") (pinfunction "2_2") (pintype "passive"))
      (node (ref "U8") (pin "1") (pinfunction "~{RESET}_1") (pintype "output"))
    )
    (net (code "80") (name "RA_1_SENSE_VCC_IN1") (class "Default")
      (node (ref "RS3") (pin "2") (pinfunction "2_2") (pintype "passive"))
      (node (ref "U10") (pin "10") (pinfunction "VIN+_10") (pintype "input"))
    )
    (net (code "81") (name "RA_1_SENSE_VCC_IN2") (class "Default")
      (node (ref "RS4") (pin "2") (pinfunction "2_2") (pintype "passive"))
      (node (ref "U9") (pin "10") (pinfunction "VIN+_10") (pintype "input"))
    )
    (net (code "82") (name "RA_1_SENSE_VCC_OUT1") (class "Default")
      (node (ref "RS3") (pin "1") (pinfunction "1_1") (pintype "passive"))
      (node (ref "U10") (pin "8") (pinfunction "VBUS_8") (pintype "input"))
      (node (ref "U10") (pin "9") (pinfunction "VIN-_9") (pintype "input"))
    )
    (net (code "83") (name "RA_1_SENSE_VCC_OUT2") (class "Default")
      (node (ref "J_V1") (pin "2") (pinfunction "2_2") (pintype "passive"))
      (node (ref "RS4") (pin "1") (pinfunction "1_1") (pintype "passive"))
      (node (ref "U9") (pin "8") (pinfunction "VBUS_8") (pintype "input"))
      (node (ref "U9") (pin "9") (pinfunction "VIN-_9") (pintype "input"))
    )
    (net (code "84") (name "unconnected-(U7A-COM0-Pad30)") (class "Default")
      (node (ref "U7") (pin "30") (pinfunction "COM0_30") (pintype "output"))
    )
    (net (code "85") (name "unconnected-(U7A-LCDCAP_R33-Pad29)") (class "Default")
      (node (ref "U7") (pin "29") (pinfunction "LCDCAP_R33_29") (pintype "passive"))
    )
    (net (code "86") (name "unconnected-(U7A-P1.0_TA0CLK_ACLK_S39-Pad34)") (class "Default")
      (node (ref "U7") (pin "34") (pinfunction "P1.0_TA0CLK_ACLK_S39_34") (pintype "bidirectional"))
    )
    (net (code "87") (name "unconnected-(U7A-P1.2_TA0.1_S37-Pad36)") (class "Default")
      (node (ref "U7") (pin "36") (pinfunction "P1.2_TA0.1_S37_36") (pintype "bidirectional"))
    )
    (net (code "88") (name "unconnected-(U7A-P1.3_TA0.2_S36-Pad37)") (class "Default")
      (node (ref "U7") (pin "37") (pinfunction "P1.3_TA0.2_S36_37") (pintype "bidirectional"))
    )
    (net (code "89") (name "unconnected-(U7A-P1.4_TA0.3_S35-Pad38)") (class "Default")
      (node (ref "U7") (pin "38") (pinfunction "P1.4_TA0.3_S35_38") (pintype "bidirectional"))
    )
    (net (code "90") (name "unconnected-(U7A-P1.5_TA0.4_S34-Pad39)") (class "Default")
      (node (ref "U7") (pin "39") (pinfunction "P1.5_TA0.4_S34_39") (pintype "bidirectional"))
    )
    (net (code "91") (name "unconnected-(U7A-P1.6_TA0.1_S33-Pad40)") (class "Default")
      (node (ref "U7") (pin "40") (pinfunction "P1.6_TA0.1_S33_40") (pintype "bidirectional"))
    )
    (net (code "92") (name "unconnected-(U7A-P1.7_TA0.2_S32-Pad41)") (class "Default")
      (node (ref "U7") (pin "41") (pinfunction "P1.7_TA0.2_S32_41") (pintype "bidirectional"))
    )
    (net (code "93") (name "unconnected-(U7A-P2.6_P2MAP6_R03-Pad23)") (class "Default")
      (node (ref "U7") (pin "23") (pinfunction "P2.6_P2MAP6_R03_23") (pintype "bidirectional"))
    )
    (net (code "94") (name "unconnected-(U7A-P2.7_P2MAP7_LCDREF_R13-Pad24)") (class "Default")
      (node (ref "U7") (pin "24") (pinfunction "P2.7_P2MAP7_LCDREF_R13_24") (pintype "bidirectional"))
    )
    (net (code "95") (name "unconnected-(U7A-P3.7_TA2.2_S24-Pad49)") (class "Default")
      (node (ref "U7") (pin "49") (pinfunction "P3.7_TA2.2_S24_49") (pintype "bidirectional"))
    )
    (net (code "96") (name "unconnected-(U7A-P4.0_TB0.0_S23-Pad50)") (class "Default")
      (node (ref "U7") (pin "50") (pinfunction "P4.0_TB0.0_S23_50") (pintype "bidirectional"))
    )
    (net (code "97") (name "unconnected-(U7A-P4.1_TB0.1_S22-Pad51)") (class "Default")
      (node (ref "U7") (pin "51") (pinfunction "P4.1_TB0.1_S22_51") (pintype "bidirectional"))
    )
    (net (code "98") (name "unconnected-(U7A-P4.2_TB0.2_S21-Pad52)") (class "Default")
      (node (ref "U7") (pin "52") (pinfunction "P4.2_TB0.2_S21_52") (pintype "bidirectional"))
    )
    (net (code "99") (name "unconnected-(U7A-P5.4_COM2_S41-Pad32)") (class "Default")
      (node (ref "U7") (pin "32") (pinfunction "P5.4_COM2_S41_32") (pintype "bidirectional"))
    )
    (net (code "100") (name "unconnected-(U7A-P5.5_COM3_S40-Pad33)") (class "Default")
      (node (ref "U7") (pin "33") (pinfunction "P5.5_COM3_S40_33") (pintype "bidirectional"))
    )
    (net (code "101") (name "unconnected-(U7A-P5.6_ADC12CLK_DMAE0-Pad16)") (class "Default")
      (node (ref "U7") (pin "16") (pinfunction "P5.6_ADC12CLK_DMAE0_16") (pintype "bidirectional"))
    )
    (net (code "102") (name "unconnected-(U7A-P6.6_CB6_A6_DAC0-Pad3)") (class "Default")
      (node (ref "U7") (pin "3") (pinfunction "P6.6_CB6_A6_DAC0_3") (pintype "bidirectional"))
    )
    (net (code "103") (name "unconnected-(U7A-P6.7_CB7_A7_DAC1-Pad4)") (class "Default")
      (node (ref "U7") (pin "4") (pinfunction "P6.7_CB7_A7_DAC1_4") (pintype "bidirectional"))
    )
    (net (code "104") (name "unconnected-(U7A-P7.4_CB8_A12-Pad5)") (class "Default")
      (node (ref "U7") (pin "5") (pinfunction "P7.4_CB8_A12_5") (pintype "bidirectional"))
    )
    (net (code "105") (name "unconnected-(U7A-P7.5_CB9_A13-Pad6)") (class "Default")
      (node (ref "U7") (pin "6") (pinfunction "P7.5_CB9_A13_6") (pintype "bidirectional"))
    )
    (net (code "106") (name "unconnected-(U7A-P7.6_CB10_A14_DAC0-Pad7)") (class "Default")
      (node (ref "U7") (pin "7") (pinfunction "P7.6_CB10_A14_DAC0_7") (pintype "bidirectional"))
    )
    (net (code "107") (name "unconnected-(U7A-P7.7_CB11_A15_DAC1-Pad8)") (class "Default")
      (node (ref "U7") (pin "8") (pinfunction "P7.7_CB11_A15_DAC1_8") (pintype "bidirectional"))
    )
    (net (code "108") (name "unconnected-(U7A-P8.0_TB0CLK_S15-Pad58)") (class "Default")
      (node (ref "U7") (pin "58") (pinfunction "P8.0_TB0CLK_S15_58") (pintype "bidirectional"))
    )
    (net (code "109") (name "unconnected-(U7A-P8.1_UCB1STE_UCA1CLK_S14-Pad59)") (class "Default")
      (node (ref "U7") (pin "59") (pinfunction "P8.1_UCB1STE_UCA1CLK_S14_59") (pintype "bidirectional"))
    )
    (net (code "110") (name "unconnected-(U7A-P8.4_UCB1CLK_UCA1STE_S11-Pad62)") (class "Default")
      (node (ref "U7") (pin "62") (pinfunction "P8.4_UCB1CLK_UCA1STE_S11_62") (pintype "bidirectional"))
    )
    (net (code "111") (name "unconnected-(U7A-PJ.0_TDO-Pad92)") (class "Default")
      (node (ref "U7") (pin "92") (pinfunction "PJ.0_TDO_92") (pintype "bidirectional"))
    )
    (net (code "112") (name "unconnected-(U7A-PJ.1_TDI_TCLK-Pad93)") (class "Default")
      (node (ref "U7") (pin "93") (pinfunction "PJ.1_TDI_TCLK_93") (pintype "bidirectional"))
    )
    (net (code "113") (name "unconnected-(U7A-PJ.2_TMS-Pad94)") (class "Default")
      (node (ref "U7") (pin "94") (pinfunction "PJ.2_TMS_94") (pintype "bidirectional"))
    )
    (net (code "114") (name "unconnected-(U7A-PJ.3_TCK-Pad95)") (class "Default")
      (node (ref "U7") (pin "95") (pinfunction "PJ.3_TCK_95") (pintype "bidirectional"))
    )
    (net (code "115") (name "unconnected-(U7A-PU.0_DP-Pad77)") (class "Default")
      (node (ref "U7") (pin "77") (pinfunction "PU.0_DP_77") (pintype "bidirectional"))
    )
    (net (code "116") (name "unconnected-(U7A-PU.1_DM-Pad79)") (class "Default")
      (node (ref "U7") (pin "79") (pinfunction "PU.1_DM_79") (pintype "bidirectional"))
    )
    (net (code "117") (name "unconnected-(U7A-PUR-Pad78)") (class "Default")
      (node (ref "U7") (pin "78") (pinfunction "PUR_78") (pintype "bidirectional"))
    )
    (net (code "118") (name "unconnected-(U7A-VBAK-Pad86)") (class "Default")
      (node (ref "U7") (pin "86") (pinfunction "VBAK_86") (pintype "passive"))
    )
    (net (code "119") (name "unconnected-(U7B-V18-Pad82)") (class "Default")
      (node (ref "U7") (pin "82") (pinfunction "V18_82") (pintype "power_in"))
    )
    (net (code "120") (name "unconnected-(U7B-VBAT-Pad87)") (class "Default")
      (node (ref "U7") (pin "87") (pinfunction "VBAT_87") (pintype "power_in"))
    )
    (net (code "121") (name "unconnected-(U7B-VBUS-Pad80)") (class "Default")
      (node (ref "U7") (pin "80") (pinfunction "VBUS_80") (pintype "power_in"))
    )
    (net (code "122") (name "unconnected-(U7B-VSSU-Pad76)") (class "Default")
      (node (ref "U7") (pin "76") (pinfunction "VSSU_76") (pintype "power_in"))
    )
    (net (code "123") (name "unconnected-(U7B-VUSB-Pad81)") (class "Default")
      (node (ref "U7") (pin "81") (pinfunction "VUSB_81") (pintype "power_in"))
    )
    (net (code "124") (name "unconnected-(U9-ALERT-Pad3)") (class "Default")
      (node (ref "U9") (pin "3") (pinfunction "ALERT_3") (pintype "output+no_connect"))
    )
  )
)
